# dual_power_supply.net
KiCad netlist of a schematic drawn in EAGLE
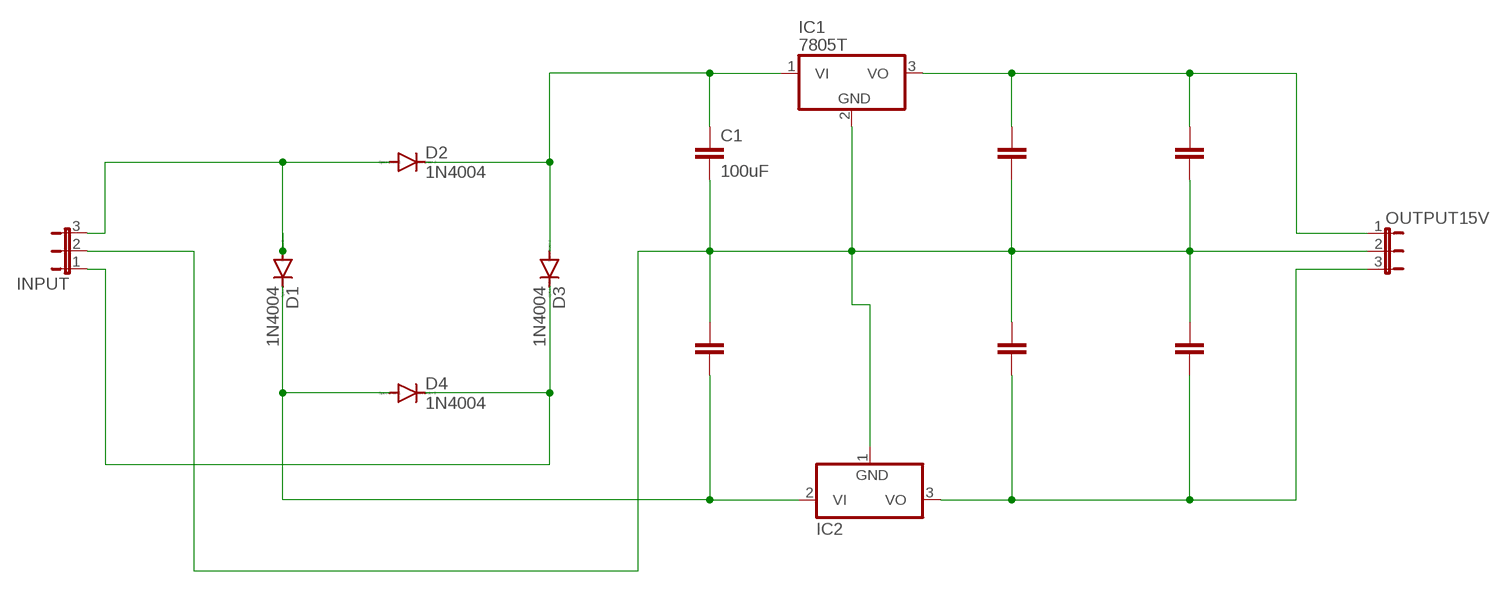
[diagram p0: schematic, sheet 1]

(export (version "E")
  (design (tool "Eeschema 10.0.6"))
  (components
    (comp (ref "C1")
      (value "100uF")
      (footprint "eagle-import:C2.5-3")
      (libsource (lib "eagle-import") (part "C2,5-3"))
    )
    (comp (ref "C2")
      (value "100uF")
      (footprint "eagle-import:C2.5-3")
      (libsource (lib "eagle-import") (part "C2,5-3"))
    )
    (comp (ref "C3")
      (value "10uF")
      (footprint "eagle-import:C2.5-3")
      (libsource (lib "eagle-import") (part "C2,5-3"))
    )
    (comp (ref "C4")
      (value "10uF")
      (footprint "eagle-import:C2.5-3")
      (libsource (lib "eagle-import") (part "C2,5-3"))
    )
    (comp (ref "C5")
      (value "0.1uF")
      (footprint "eagle-import:C2.5-3")
      (libsource (lib "eagle-import") (part "C2,5-3"))
    )
    (comp (ref "C6")
      (value "0.1uF")
      (footprint "eagle-import:C2.5-3")
      (libsource (lib "eagle-import") (part "C2,5-3"))
    )
    (comp (ref "D1")
      (value "1N4004")
      (footprint "eagle-import:DO41-10")
      (libsource (lib "eagle-import") (part "1N4004"))
    )
    (comp (ref "D2")
      (value "1N4004")
      (footprint "eagle-import:DO41-10")
      (libsource (lib "eagle-import") (part "1N4004"))
    )
    (comp (ref "D3")
      (value "1N4004")
      (footprint "eagle-import:DO41-10")
      (libsource (lib "eagle-import") (part "1N4004"))
    )
    (comp (ref "D4")
      (value "1N4004")
      (footprint "eagle-import:DO41-10")
      (libsource (lib "eagle-import") (part "1N4004"))
    )
    (comp (ref "IC1")
      (value "7805T")
      (footprint "eagle-import:TO220H")
      (libsource (lib "eagle-import") (part "78T05"))
    )
    (comp (ref "IC2")
      (value "7905T")
      (footprint "eagle-import:TO220H")
      (libsource (lib "eagle-import") (part "79T05"))
    )
    (comp (ref "INPUT")
      (value "JP2E")
      (footprint "eagle-import:JP2")
      (libsource (lib "eagle-import") (part "JP2E"))
    )
    (comp (ref "OUTPUT15V")
      (value "JP2E")
      (footprint "eagle-import:JP2")
      (libsource (lib "eagle-import") (part "JP2E"))
    )
  )
  (nets
    (net (code "1") (name "Net-(D1-PadA)") (class "Default")
      (node (ref "D1") (pin "A") (pinfunction "A_A") (pintype "passive"))
      (node (ref "D2") (pin "A") (pinfunction "A_A") (pintype "passive"))
      (node (ref "INPUT") (pin "3") (pinfunction "3_3") (pintype "passive"))
    )
    (net (code "2") (name "Net-(D3-PadC)") (class "Default")
      (node (ref "D3") (pin "C") (pinfunction "C_C") (pintype "passive"))
      (node (ref "D4") (pin "C") (pinfunction "C_C") (pintype "passive"))
      (node (ref "INPUT") (pin "1") (pinfunction "1_1") (pintype "passive"))
    )
    (net (code "3") (name "Net-(IC1-GND)") (class "Default")
      (node (ref "C1") (pin "2") (pinfunction "2_2") (pintype "passive"))
      (node (ref "C2") (pin "1") (pinfunction "1_1") (pintype "passive"))
      (node (ref "C3") (pin "2") (pinfunction "2_2") (pintype "passive"))
      (node (ref "C4") (pin "1") (pinfunction "1_1") (pintype "passive"))
      (node (ref "C5") (pin "2") (pinfunction "2_2") (pintype "passive"))
      (node (ref "C6") (pin "1") (pinfunction "1_1") (pintype "passive"))
      (node (ref "IC1") (pin "2") (pinfunction "GND_2") (pintype "passive"))
      (node (ref "IC2") (pin "1") (pinfunction "GND_1") (pintype "passive"))
      (node (ref "INPUT") (pin "2") (pinfunction "2_2") (pintype "passive"))
      (node (ref "OUTPUT15V") (pin "2") (pinfunction "2_2") (pintype "passive"))
    )
    (net (code "4") (name "Net-(IC1-VI)") (class "Default")
      (node (ref "C1") (pin "1") (pinfunction "1_1") (pintype "passive"))
      (node (ref "D2") (pin "C") (pinfunction "C_C") (pintype "passive"))
      (node (ref "D3") (pin "A") (pinfunction "A_A") (pintype "passive"))
      (node (ref "IC1") (pin "1") (pinfunction "VI_1") (pintype "input"))
    )
    (net (code "5") (name "Net-(IC1-VO)") (class "Default")
      (node (ref "C3") (pin "1") (pinfunction "1_1") (pintype "passive"))
      (node (ref "C5") (pin "1") (pinfunction "1_1") (pintype "passive"))
      (node (ref "IC1") (pin "3") (pinfunction "VO_3") (pintype "passive"))
      (node (ref "OUTPUT15V") (pin "1") (pinfunction "1_1") (pintype "passive"))
    )
    (net (code "6") (name "Net-(IC2-VI)") (class "Default")
      (node (ref "C2") (pin "2") (pinfunction "2_2") (pintype "passive"))
      (node (ref "D1") (pin "C") (pinfunction "C_C") (pintype "passive"))
      (node (ref "D4") (pin "A") (pinfunction "A_A") (pintype "passive"))
      (node (ref "IC2") (pin "2") (pinfunction "VI_2") (pintype "input"))
    )
    (net (code "7") (name "Net-(IC2-VO)") (class "Default")
      (node (ref "C4") (pin "2") (pinfunction "2_2") (pintype "passive"))
      (node (ref "C6") (pin "2") (pinfunction "2_2") (pintype "passive"))
      (node (ref "IC2") (pin "3") (pinfunction "VO_3") (pintype "passive"))
      (node (ref "OUTPUT15V") (pin "3") (pinfunction "3_3") (pintype "passive"))
    )
  )
)
